# Filter_Capacitors_-_FOTA_ICSP.net
KiCad netlist of a schematic drawn in Altium Designer
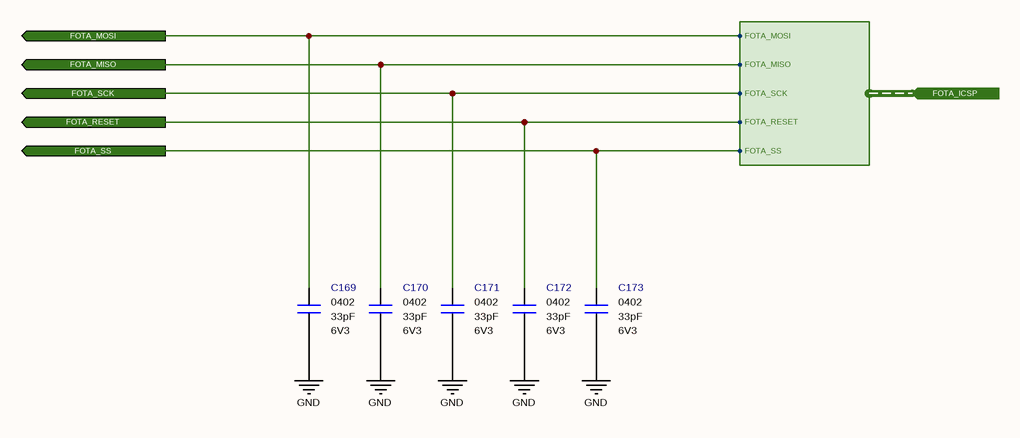
[diagram p0: Filter Capacitors - FOTA ICSP.SchDoc]

(export (version "E")
  (design (tool "Eeschema 10.0.6"))
  (components
    (comp (ref "C169")
      (value "33pF")
      (footprint "CAPACITOR_0402")
      (description "Capacitor - 33pF [0402] (Ceramic)")
      (fields
        (field (name "TOLERANCE") "10%")
        (field (name "CASE") "0402")
        (field (name "VOLTAGE") "6V3")
        (field (name "MANUFACTURER PART NUMBER") "C0402C330J9RACAUTO")
      )
      (libsource (lib "Ovoo_Library") (part "Capacitor - 33pF [0402-6V3]"))
    )
    (comp (ref "C170")
      (value "33pF")
      (footprint "CAPACITOR_0402")
      (description "Capacitor - 33pF [0402] (Ceramic)")
      (fields
        (field (name "TOLERANCE") "10%")
        (field (name "CASE") "0402")
        (field (name "VOLTAGE") "6V3")
        (field (name "MANUFACTURER PART NUMBER") "C0402C330J9RACAUTO")
      )
      (libsource (lib "Ovoo_Library") (part "Capacitor - 33pF [0402-6V3]"))
    )
    (comp (ref "C171")
      (value "33pF")
      (footprint "CAPACITOR_0402")
      (description "Capacitor - 33pF [0402] (Ceramic)")
      (fields
        (field (name "TOLERANCE") "10%")
        (field (name "CASE") "0402")
        (field (name "VOLTAGE") "6V3")
        (field (name "MANUFACTURER PART NUMBER") "C0402C330J9RACAUTO")
      )
      (libsource (lib "Ovoo_Library") (part "Capacitor - 33pF [0402-6V3]"))
    )
    (comp (ref "C172")
      (value "33pF")
      (footprint "CAPACITOR_0402")
      (description "Capacitor - 33pF [0402] (Ceramic)")
      (fields
        (field (name "TOLERANCE") "10%")
        (field (name "CASE") "0402")
        (field (name "VOLTAGE") "6V3")
        (field (name "MANUFACTURER PART NUMBER") "C0402C330J9RACAUTO")
      )
      (libsource (lib "Ovoo_Library") (part "Capacitor - 33pF [0402-6V3]"))
    )
    (comp (ref "C173")
      (value "33pF")
      (footprint "CAPACITOR_0402")
      (description "Capacitor - 33pF [0402] (Ceramic)")
      (fields
        (field (name "TOLERANCE") "10%")
        (field (name "CASE") "0402")
        (field (name "VOLTAGE") "6V3")
        (field (name "MANUFACTURER PART NUMBER") "C0402C330J9RACAUTO")
      )
      (libsource (lib "Ovoo_Library") (part "Capacitor - 33pF [0402-6V3]"))
    )
  )
  (nets
    (net (code "2") (name "/FOTA_MISO") (class "Default")
      (node (ref "C170") (pin "2") (pinfunction "2_2") (pintype "passive"))
    )
    (net (code "3") (name "/FOTA_MOSI") (class "Default")
      (node (ref "C169") (pin "2") (pinfunction "2_2") (pintype "passive"))
    )
    (net (code "4") (name "/FOTA_RESET") (class "Default")
      (node (ref "C172") (pin "2") (pinfunction "2_2") (pintype "passive"))
    )
    (net (code "5") (name "/FOTA_SCK") (class "Default")
      (node (ref "C171") (pin "2") (pinfunction "2_2") (pintype "passive"))
    )
    (net (code "6") (name "/FOTA_SS") (class "Default")
      (node (ref "C173") (pin "2") (pinfunction "2_2") (pintype "passive"))
    )
    (net (code "8") (name "GND") (class "Default")
      (node (ref "C169") (pin "1") (pinfunction "1_1") (pintype "passive"))
      (node (ref "C170") (pin "1") (pinfunction "1_1") (pintype "passive"))
      (node (ref "C171") (pin "1") (pinfunction "1_1") (pintype "passive"))
      (node (ref "C172") (pin "1") (pinfunction "1_1") (pintype "passive"))
      (node (ref "C173") (pin "1") (pinfunction "1_1") (pintype "passive"))
    )
  )
)
